# rpi-clock.net
KiCad netlist of a schematic drawn in EAGLE
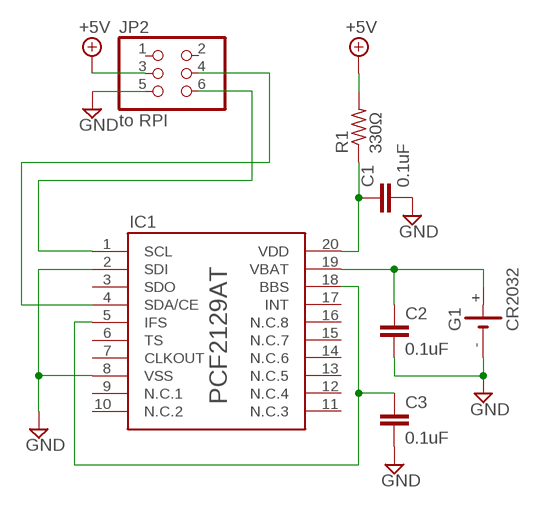
[diagram p0: schematic, sheet 1]

(export (version "E")
  (design (tool "Eeschema 10.0.6"))
  (components
    (comp (ref "C1")
      (value "0.1uF")
      (footprint "eagle-import:C0504")
      (libsource (lib "eagle-import") (part "C-EUC0504"))
    )
    (comp (ref "C2")
      (value "0.1uF")
      (footprint "eagle-import:C0504")
      (libsource (lib "eagle-import") (part "C-EUC0504"))
    )
    (comp (ref "C3")
      (value "0.1uF")
      (footprint "eagle-import:C0504")
      (libsource (lib "eagle-import") (part "C-EUC0504"))
    )
    (comp (ref "G1")
      (value "CR2032")
      (footprint "eagle-import:HU2032")
      (libsource (lib "eagle-import") (part "HU2032"))
    )
    (comp (ref "IC1")
      (value "PCF2129AT")
      (footprint "eagle-import:SO20")
      (libsource (lib "eagle-import") (part "PCF2129AT"))
    )
    (comp (ref "JP2")
      (value "to RPI")
      (footprint "eagle-import:2X03")
      (libsource (lib "eagle-import") (part "PINHD-2X3"))
    )
    (comp (ref "R1")
      (value "330Ω")
      (footprint "eagle-import:M0805")
      (libsource (lib "eagle-import") (part "R-US_M0805"))
    )
  )
  (nets
    (net (code "1") (name "+5V") (class "Default")
      (node (ref "JP2") (pin "3") (pinfunction "3_3") (pintype "passive"))
      (node (ref "R1") (pin "2") (pinfunction "2_2") (pintype "passive"))
    )
    (net (code "2") (name "GND") (class "Default")
      (node (ref "C1") (pin "2") (pinfunction "2_2") (pintype "passive"))
      (node (ref "C2") (pin "2") (pinfunction "2_2") (pintype "passive"))
      (node (ref "C3") (pin "2") (pinfunction "2_2") (pintype "passive"))
      (node (ref "G1") (pin "-") (pinfunction "-_-") (pintype "passive"))
      (node (ref "IC1") (pin "2") (pinfunction "SDI_2") (pintype "bidirectional"))
      (node (ref "IC1") (pin "8") (pinfunction "VSS_8") (pintype "bidirectional"))
      (node (ref "JP2") (pin "5") (pinfunction "5_5") (pintype "passive"))
    )
    (net (code "3") (name "Net-(IC1-BBS)") (class "Default")
      (node (ref "C3") (pin "1") (pinfunction "1_1") (pintype "passive"))
      (node (ref "IC1") (pin "18") (pinfunction "BBS_18") (pintype "bidirectional"))
      (node (ref "IC1") (pin "5") (pinfunction "IFS_5") (pintype "bidirectional"))
    )
    (net (code "4") (name "Net-(IC1-SCL)") (class "Default")
      (node (ref "IC1") (pin "1") (pinfunction "SCL_1") (pintype "bidirectional"))
      (node (ref "JP2") (pin "6") (pinfunction "6_6") (pintype "passive"))
    )
    (net (code "5") (name "Net-(IC1-SDA{slash}CE)") (class "Default")
      (node (ref "IC1") (pin "4") (pinfunction "SDA/CE_4") (pintype "bidirectional"))
      (node (ref "JP2") (pin "4") (pinfunction "4_4") (pintype "passive"))
    )
    (net (code "6") (name "Net-(IC1-VBAT)") (class "Default")
      (node (ref "C2") (pin "1") (pinfunction "1_1") (pintype "passive"))
      (node (ref "G1") (pin "+") (pinfunction "+_+") (pintype "passive"))
      (node (ref "IC1") (pin "19") (pinfunction "VBAT_19") (pintype "bidirectional"))
    )
    (net (code "7") (name "Net-(IC1-VDD)") (class "Default")
      (node (ref "C1") (pin "1") (pinfunction "1_1") (pintype "passive"))
      (node (ref "IC1") (pin "20") (pinfunction "VDD_20") (pintype "bidirectional"))
      (node (ref "R1") (pin "1") (pinfunction "1_1") (pintype "passive"))
    )
    (net (code "8") (name "unconnected-(G1-+-Pad+@2)") (class "Default")
      (node (ref "G1") (pin "+@2") (pinfunction "+_+@2") (pintype "passive"))
    )
    (net (code "9") (name "unconnected-(IC1-CLKOUT-Pad7)") (class "Default")
      (node (ref "IC1") (pin "7") (pinfunction "CLKOUT_7") (pintype "bidirectional"))
    )
    (net (code "10") (name "unconnected-(IC1-INT-Pad17)") (class "Default")
      (node (ref "IC1") (pin "17") (pinfunction "INT_17") (pintype "bidirectional"))
    )
    (net (code "11") (name "unconnected-(IC1-N.C.1-Pad9)") (class "Default")
      (node (ref "IC1") (pin "9") (pinfunction "N.C.1_9") (pintype "bidirectional"))
    )
    (net (code "12") (name "unconnected-(IC1-N.C.2-Pad10)") (class "Default")
      (node (ref "IC1") (pin "10") (pinfunction "N.C.2_10") (pintype "bidirectional"))
    )
    (net (code "13") (name "unconnected-(IC1-N.C.3-Pad11)") (class "Default")
      (node (ref "IC1") (pin "11") (pinfunction "N.C.3_11") (pintype "bidirectional"))
    )
    (net (code "14") (name "unconnected-(IC1-N.C.4-Pad12)") (class "Default")
      (node (ref "IC1") (pin "12") (pinfunction "N.C.4_12") (pintype "bidirectional"))
    )
    (net (code "15") (name "unconnected-(IC1-N.C.5-Pad13)") (class "Default")
      (node (ref "IC1") (pin "13") (pinfunction "N.C.5_13") (pintype "bidirectional"))
    )
    (net (code "16") (name "unconnected-(IC1-N.C.6-Pad14)") (class "Default")
      (node (ref "IC1") (pin "14") (pinfunction "N.C.6_14") (pintype "bidirectional"))
    )
    (net (code "17") (name "unconnected-(IC1-N.C.7-Pad15)") (class "Default")
      (node (ref "IC1") (pin "15") (pinfunction "N.C.7_15") (pintype "bidirectional"))
    )
    (net (code "18") (name "unconnected-(IC1-N.C.8-Pad16)") (class "Default")
      (node (ref "IC1") (pin "16") (pinfunction "N.C.8_16") (pintype "bidirectional"))
    )
    (net (code "19") (name "unconnected-(IC1-SDO-Pad3)") (class "Default")
      (node (ref "IC1") (pin "3") (pinfunction "SDO_3") (pintype "bidirectional"))
    )
    (net (code "20") (name "unconnected-(IC1-TS-Pad6)") (class "Default")
      (node (ref "IC1") (pin "6") (pinfunction "TS_6") (pintype "bidirectional"))
    )
    (net (code "21") (name "unconnected-(JP2-Pad1)") (class "Default")
      (node (ref "JP2") (pin "1") (pinfunction "1_1") (pintype "passive"))
    )
    (net (code "22") (name "unconnected-(JP2-Pad2)") (class "Default")
      (node (ref "JP2") (pin "2") (pinfunction "2_2") (pintype "passive"))
    )
  )
)
